# POWER.net
KiCad netlist of a schematic drawn in Altium Designer
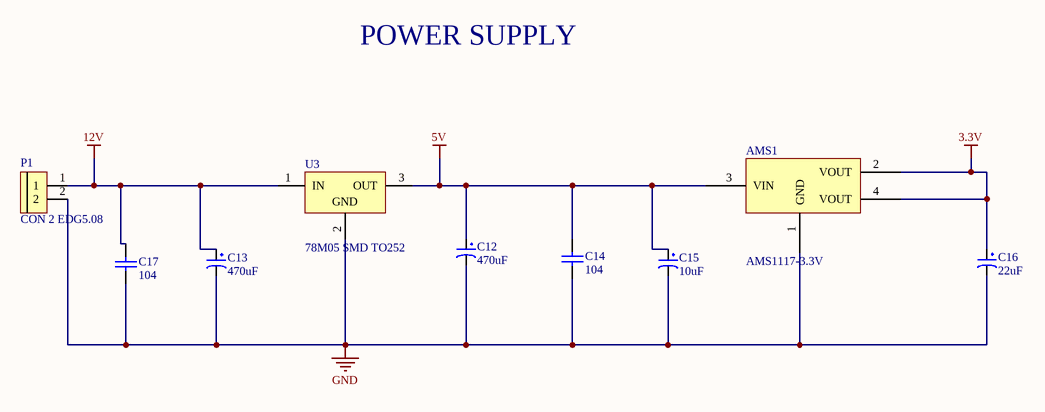
[diagram p0: POWER.SchDoc]

(export (version "E")
  (design (tool "Eeschema 10.0.6"))
  (components
    (comp (ref "AMS1")
      (value "AMS1117-3.3V")
      (footprint "SOT223")
      (description "Dán")
      (libsource (lib "Altium_Lib_by_KhueNguyenCreator") (part "AMS1117 SMD"))
    )
    (comp (ref "C12")
      (value "470uF")
      (footprint "tu hoa 8mm")
      (description "Cắm")
      (libsource (lib "Altium_Lib_by_KhueNguyenCreator") (part "Tu Hoa 470uF 16V 8x11"))
    )
    (comp (ref "C13")
      (value "470uF")
      (footprint "tu hoa 8mm")
      (description "Cắm")
      (libsource (lib "Altium_Lib_by_KhueNguyenCreator") (part "Tu Hoa 470uF 16V 8x11"))
    )
    (comp (ref "C14")
      (value "104")
      (footprint "tu 1206")
      (description "Dán")
      (libsource (lib "Altium_Lib_by_KhueNguyenCreator") (part "Tu 1206 104 50V 20%"))
    )
    (comp (ref "C15")
      (value "10uF")
      (footprint "tu tantalum smd3216")
      (description "Dán")
      (libsource (lib "Altium_Lib_by_KhueNguyenCreator") (part "Tu tantalum 10uF 16V SMD3216"))
    )
    (comp (ref "C16")
      (value "22uF")
      (footprint "tu tantalum smd6032")
      (description "Dán")
      (libsource (lib "Altium_Lib_by_KhueNguyenCreator") (part "Tu tantalum 22uF 25V SMD6032"))
    )
    (comp (ref "C17")
      (value "104")
      (footprint "tu 1206")
      (description "Dán")
      (libsource (lib "Altium_Lib_by_KhueNguyenCreator") (part "Tu 1206 104 50V 20%"))
    )
    (comp (ref "P1")
      (value "CON 2 EDG5.08")
      (footprint "CON 2 2EDG5.08")
      (description "Cắm")
      (libsource (lib "Altium_Lib_by_KhueNguyenCreator") (part "CON 2 EDG5.08"))
    )
    (comp (ref "U3")
      (value "78M05 SMD TO252")
      (footprint "TO252")
      (description "Dán")
      (libsource (lib "Altium_Lib_by_KhueNguyenCreator") (part "78M05 SMD TO252"))
    )
  )
  (nets
    (net (code "1") (name "3.3V") (class "Default")
      (node (ref "AMS1") (pin "2") (pinfunction "VOUT_2") (pintype "passive"))
      (node (ref "AMS1") (pin "4") (pinfunction "VOUT_4") (pintype "passive"))
      (node (ref "C16") (pin "1") (pinfunction "1_1") (pintype "passive"))
    )
    (net (code "2") (name "5V") (class "Default")
      (node (ref "AMS1") (pin "3") (pinfunction "VIN_3") (pintype "passive"))
      (node (ref "C12") (pin "1") (pinfunction "1_1") (pintype "passive"))
      (node (ref "C14") (pin "1") (pinfunction "1_1") (pintype "passive"))
      (node (ref "C15") (pin "1") (pinfunction "1_1") (pintype "passive"))
      (node (ref "U3") (pin "3") (pinfunction "OUT_3") (pintype "power_in"))
    )
    (net (code "3") (name "12V") (class "Default")
      (node (ref "C13") (pin "1") (pinfunction "1_1") (pintype "passive"))
      (node (ref "C17") (pin "1") (pinfunction "1_1") (pintype "passive"))
      (node (ref "P1") (pin "1") (pinfunction "1_1") (pintype "passive"))
      (node (ref "U3") (pin "1") (pinfunction "IN_1") (pintype "power_in"))
    )
    (net (code "4") (name "GND") (class "Default")
      (node (ref "AMS1") (pin "1") (pinfunction "GND_1") (pintype "passive"))
      (node (ref "C12") (pin "2") (pinfunction "2_2") (pintype "passive"))
      (node (ref "C13") (pin "2") (pinfunction "2_2") (pintype "passive"))
      (node (ref "C14") (pin "2") (pinfunction "2_2") (pintype "passive"))
      (node (ref "C15") (pin "2") (pinfunction "2_2") (pintype "passive"))
      (node (ref "C16") (pin "2") (pinfunction "2_2") (pintype "passive"))
      (node (ref "C17") (pin "2") (pinfunction "2_2") (pintype "passive"))
      (node (ref "P1") (pin "2") (pinfunction "2_2") (pintype "passive"))
      (node (ref "U3") (pin "2") (pinfunction "GND_2") (pintype "power_in"))
    )
  )
)
